# working.net
KiCad netlist of a schematic drawn in EAGLE
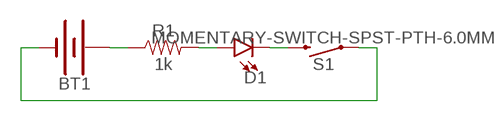
[diagram p0: schematic, sheet 1]

(export (version "E")
  (design (tool "Eeschema 10.0.6"))
  (components
    (comp (ref "BT1")
      (value "BATTERY-20MM_SMD_4LEGS")
      (footprint "eagle-import:BATTCON_20MM_4LEGS")
      (libsource (lib "eagle-import") (part "BATTERY-20MM_SMD_4LEGS"))
    )
    (comp (ref "D1")
      (value "LED5MM")
      (footprint "eagle-import:LED_5MM")
      (libsource (lib "eagle-import") (part "LED5MM"))
    )
    (comp (ref "R1")
      (value "1k")
      (footprint "eagle-import:AXIAL-0.3")
      (libsource (lib "eagle-import") (part "1KOHM-HORIZ-1/4W-1%"))
    )
    (comp (ref "S1")
      (value "MOMENTARY-SWITCH-SPST-PTH-6.0MM")
      (footprint "eagle-import:TACTILE_SWITCH_PTH_6.0MM")
      (libsource (lib "eagle-import") (part "MOMENTARY-SWITCH-SPST-PTH-6.0MM"))
    )
  )
  (nets
    (net (code "1") (name "Net-(BT1--)") (class "Default")
      (node (ref "BT1") (pin "NEGATIVE") (pinfunction "-_NEGATIVE") (pintype "power_in"))
      (node (ref "S1") (pin "1") (pinfunction "1_1") (pintype "passive"))
    )
    (net (code "2") (name "Net-(D1-C)") (class "Default")
      (node (ref "D1") (pin "K") (pinfunction "C_K") (pintype "passive"))
      (node (ref "S1") (pin "3") (pinfunction "2_3") (pintype "passive"))
    )
    (net (code "3") (name "Net-(R1-1)") (class "Default")
      (node (ref "BT1") (pin "POSITIVE@1") (pinfunction "+_POSITIVE@1") (pintype "power_in"))
      (node (ref "BT1") (pin "POSITIVE@2") (pinfunction "+_POSITIVE@2") (pintype "power_in"))
      (node (ref "BT1") (pin "POSITIVE@3") (pinfunction "+_POSITIVE@3") (pintype "power_in"))
      (node (ref "BT1") (pin "POSITIVE@4") (pinfunction "+_POSITIVE@4") (pintype "power_in"))
      (node (ref "R1") (pin "P$1") (pinfunction "1_P$1") (pintype "passive"))
    )
    (net (code "4") (name "Net-(R1-2)") (class "Default")
      (node (ref "D1") (pin "A") (pinfunction "A_A") (pintype "passive"))
      (node (ref "R1") (pin "P$2") (pinfunction "2_P$2") (pintype "passive"))
    )
  )
)
